# MCU_DBG.net
KiCad netlist of a schematic drawn in Altium Designer
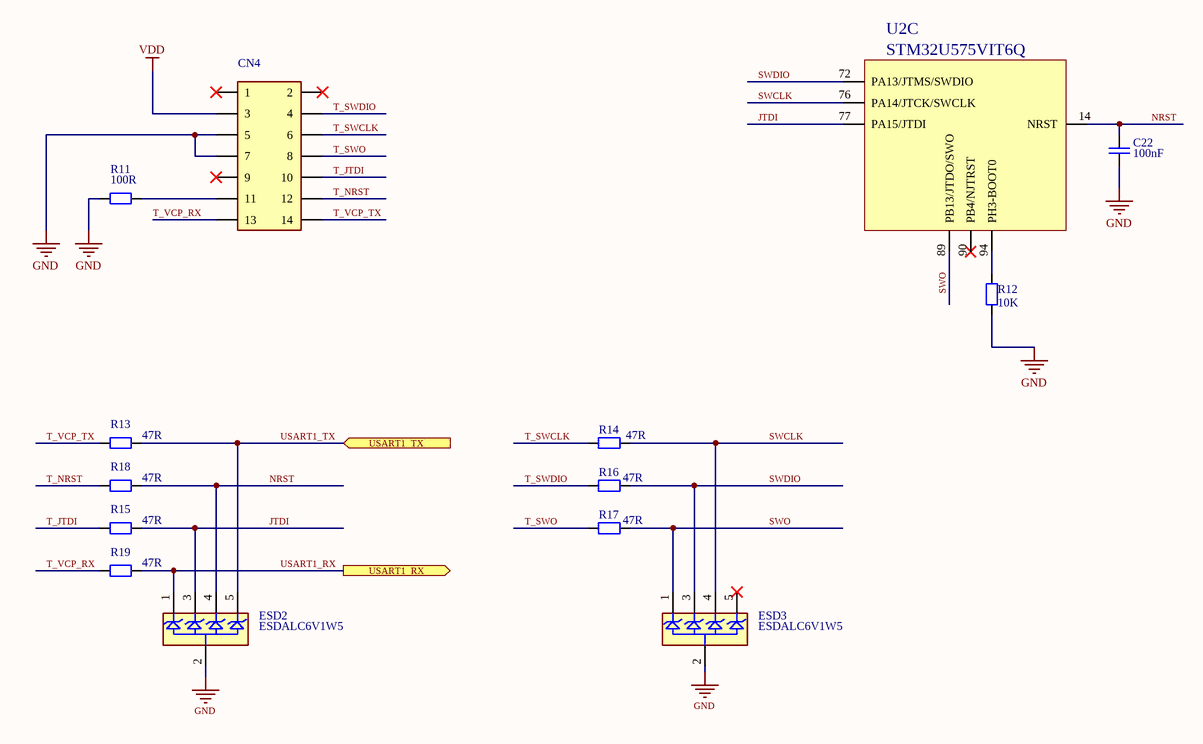
[diagram p0: MCU_DBG.SchDoc]

(export (version "E")
  (design (tool "Eeschema 10.0.6"))
  (components
    (comp (ref "C22")
      (value "100nF")
      (footprint "CAP_SM0805_YAGEOCC2_N")
      (description "CAP 100nF SM0805 X7R 50V YAGEO CC2")
      (fields
        (field (name "MANUFACTURER") "Yageo")
        (field (name "MANUFACTURER PART NUMBER") "CC0805KRX7R9BB104")
      )
      (libsource (lib "Yageo") (part "CC0805KRX7R9BB104"))
    )
    (comp (ref "CN4")
      (value "20021511-00014T4LF")
      (footprint "2002151100014T4LF")
      (description "1.27mm (0.05in.) pitch, Shrouded header, 14 contacts")
      (fields (field (name "MANUFACTURER") "Amphenol ICC"))
      (libsource (lib "header_shrouded") (part "20021511-00014T4LF"))
    )
    (comp (ref "ESD2")
      (value "ESDALC6V1W5")
      (footprint "ESDALC6V1W5")
      (fields (field (name "MANUFACTURER") "ST"))
      (libsource (lib "diode") (part "ESDALC6V1W5"))
    )
    (comp (ref "ESD3")
      (value "ESDALC6V1W5")
      (footprint "ESDALC6V1W5")
      (fields (field (name "MANUFACTURER") "ST"))
      (libsource (lib "diode") (part "ESDALC6V1W5"))
    )
    (comp (ref "R11")
      (value "100R")
      (footprint "RES_SM0805_YAGEORC_N")
      (description "RES 100R SM0805 YAGEO RC_L")
      (fields
        (field (name "MANUFACTURER") "Yageo")
        (field (name "MANUFACTURER PART NUMBER") "RC0805FR-07100RL")
      )
      (libsource (lib "Yageo") (part "RC0805FR-07100RL"))
    )
    (comp (ref "R12")
      (value "10K")
      (footprint "RES_SM0805_YAGEORC_N")
      (description "RES 10K SM0805 YAGEO RC_L")
      (fields
        (field (name "MANUFACTURER") "Yageo")
        (field (name "MANUFACTURER PART NUMBER") "RC0805FR-0710KL")
      )
      (libsource (lib "Yageo") (part "RC0805FR-0710KL"))
    )
    (comp (ref "R13")
      (value "47R")
      (footprint "RES_SM0805_YAGEORC_N")
      (description "RES 47R SM0805 YAGEO RC_L")
      (fields
        (field (name "MANUFACTURER") "Yageo")
        (field (name "MANUFACTURER PART NUMBER") "RC0805FR-0747RL")
      )
      (libsource (lib "Yageo") (part "RC0805FR-0747RL"))
    )
    (comp (ref "R14")
      (value "47R")
      (footprint "RES_SM0805_YAGEORC_N")
      (description "RES 47R SM0805 YAGEO RC_L")
      (fields
        (field (name "MANUFACTURER") "Yageo")
        (field (name "MANUFACTURER PART NUMBER") "RC0805FR-0747RL")
      )
      (libsource (lib "Yageo") (part "RC0805FR-0747RL"))
    )
    (comp (ref "R15")
      (value "47R")
      (footprint "RES_SM0805_YAGEORC_N")
      (description "RES 47R SM0805 YAGEO RC_L")
      (fields
        (field (name "MANUFACTURER") "Yageo")
        (field (name "MANUFACTURER PART NUMBER") "RC0805FR-0747RL")
      )
      (libsource (lib "Yageo") (part "RC0805FR-0747RL"))
    )
    (comp (ref "R16")
      (value "47R")
      (footprint "RES_SM0805_YAGEORC_N")
      (description "RES 47R SM0805 YAGEO RC_L")
      (fields
        (field (name "MANUFACTURER") "Yageo")
        (field (name "MANUFACTURER PART NUMBER") "RC0805FR-0747RL")
      )
      (libsource (lib "Yageo") (part "RC0805FR-0747RL"))
    )
    (comp (ref "R17")
      (value "47R")
      (footprint "RES_SM0805_YAGEORC_N")
      (description "RES 47R SM0805 YAGEO RC_L")
      (fields
        (field (name "MANUFACTURER") "Yageo")
        (field (name "MANUFACTURER PART NUMBER") "RC0805FR-0747RL")
      )
      (libsource (lib "Yageo") (part "RC0805FR-0747RL"))
    )
    (comp (ref "R18")
      (value "47R")
      (footprint "RES_SM0805_YAGEORC_N")
      (description "RES 47R SM0805 YAGEO RC_L")
      (fields
        (field (name "MANUFACTURER") "Yageo")
        (field (name "MANUFACTURER PART NUMBER") "RC0805FR-0747RL")
      )
      (libsource (lib "Yageo") (part "RC0805FR-0747RL"))
    )
    (comp (ref "R19")
      (value "47R")
      (footprint "RES_SM0805_YAGEORC_N")
      (description "RES 47R SM0805 YAGEO RC_L")
      (fields
        (field (name "MANUFACTURER") "Yageo")
        (field (name "MANUFACTURER PART NUMBER") "RC0805FR-0747RL")
      )
      (libsource (lib "Yageo") (part "RC0805FR-0747RL"))
    )
    (comp (ref "U2")
      (value "STM32U575VIT6Q")
      (footprint "STM32U575VI")
      (fields (field (name "MANUFACTURER") "ST"))
      (libsource (lib "Microcontroladores") (part "STM32U575VI_1"))
    )
  )
  (nets
    (net (code "1") (name "/JTDI") (class "Default")
      (node (ref "ESD2") (pin "3") (pinfunction "I/02_3") (pintype "passive"))
      (node (ref "R15") (pin "2") (pintype "passive"))
      (node (ref "U2") (pin "77") (pinfunction "PA15/JTDI_77") (pintype "passive"))
    )
    (net (code "2") (name "/NRST") (class "Default")
      (node (ref "C22") (pin "1") (pintype "passive"))
      (node (ref "ESD2") (pin "4") (pinfunction "I/03_4") (pintype "passive"))
      (node (ref "R18") (pin "2") (pintype "passive"))
      (node (ref "U2") (pin "14") (pinfunction "NRST_14") (pintype "passive"))
    )
    (net (code "3") (name "/SWCLK") (class "Default")
      (node (ref "ESD3") (pin "4") (pinfunction "I/03_4") (pintype "passive"))
      (node (ref "R14") (pin "2") (pintype "passive"))
      (node (ref "U2") (pin "76") (pinfunction "PA14/JTCK/SWCLK_76") (pintype "passive"))
    )
    (net (code "4") (name "/SWDIO") (class "Default")
      (node (ref "ESD3") (pin "3") (pinfunction "I/02_3") (pintype "passive"))
      (node (ref "R16") (pin "2") (pintype "passive"))
      (node (ref "U2") (pin "72") (pinfunction "PA13/JTMS/SWDIO_72") (pintype "passive"))
    )
    (net (code "5") (name "/SWO") (class "Default")
      (node (ref "ESD3") (pin "1") (pinfunction "I/01_1") (pintype "passive"))
      (node (ref "R17") (pin "2") (pintype "passive"))
      (node (ref "U2") (pin "89") (pinfunction "PB13/JTDO/SWO_89") (pintype "passive"))
    )
    (net (code "6") (name "/T_JTDI") (class "Default")
      (node (ref "CN4") (pin "10") (pinfunction "10_10") (pintype "passive"))
      (node (ref "R15") (pin "1") (pintype "passive"))
    )
    (net (code "7") (name "/T_NRST") (class "Default")
      (node (ref "CN4") (pin "12") (pinfunction "12_12") (pintype "passive"))
      (node (ref "R18") (pin "1") (pintype "passive"))
    )
    (net (code "8") (name "/T_SWCLK") (class "Default")
      (node (ref "CN4") (pin "6") (pinfunction "6_6") (pintype "passive"))
      (node (ref "R14") (pin "1") (pintype "passive"))
    )
    (net (code "9") (name "/T_SWDIO") (class "Default")
      (node (ref "CN4") (pin "4") (pinfunction "4_4") (pintype "passive"))
      (node (ref "R16") (pin "1") (pintype "passive"))
    )
    (net (code "10") (name "/T_SWO") (class "Default")
      (node (ref "CN4") (pin "8") (pinfunction "8_8") (pintype "passive"))
      (node (ref "R17") (pin "1") (pintype "passive"))
    )
    (net (code "11") (name "/T_VCP_RX") (class "Default")
      (node (ref "CN4") (pin "13") (pinfunction "13_13") (pintype "passive"))
      (node (ref "R19") (pin "1") (pintype "passive"))
    )
    (net (code "12") (name "/T_VCP_TX") (class "Default")
      (node (ref "CN4") (pin "14") (pinfunction "14_14") (pintype "passive"))
      (node (ref "R13") (pin "1") (pintype "passive"))
    )
    (net (code "13") (name "/USART1_RX") (class "Default")
      (node (ref "ESD2") (pin "1") (pinfunction "I/01_1") (pintype "passive"))
      (node (ref "R19") (pin "2") (pintype "passive"))
    )
    (net (code "14") (name "/USART1_TX") (class "Default")
      (node (ref "ESD2") (pin "5") (pinfunction "I/04_5") (pintype "passive"))
      (node (ref "R13") (pin "2") (pintype "passive"))
    )
    (net (code "15") (name "GND") (class "Default")
      (node (ref "C22") (pin "2") (pintype "passive"))
      (node (ref "CN4") (pin "5") (pinfunction "5_5") (pintype "passive"))
      (node (ref "CN4") (pin "7") (pinfunction "7_7") (pintype "passive"))
      (node (ref "ESD2") (pin "2") (pinfunction "GND_2") (pintype "passive"))
      (node (ref "ESD3") (pin "2") (pinfunction "GND_2") (pintype "passive"))
      (node (ref "R11") (pin "1") (pintype "passive"))
      (node (ref "R12") (pin "1") (pintype "passive"))
    )
    (net (code "16") (name "Net-(CN4-Pad11)") (class "Default")
      (node (ref "CN4") (pin "11") (pinfunction "11_11") (pintype "passive"))
      (node (ref "R11") (pin "2") (pintype "passive"))
    )
    (net (code "17") (name "Net-(U2C-PH3-BOOT0)") (class "Default")
      (node (ref "R12") (pin "2") (pintype "passive"))
      (node (ref "U2") (pin "94") (pinfunction "PH3-BOOT0_94") (pintype "passive"))
    )
    (net (code "18") (name "VDD") (class "Default")
      (node (ref "CN4") (pin "3") (pinfunction "3_3") (pintype "passive"))
    )
    (net (code "19") (name "unconnected-(CN4-Pad1)") (class "Default")
      (node (ref "CN4") (pin "1") (pinfunction "1_1") (pintype "passive+no_connect"))
    )
    (net (code "20") (name "unconnected-(CN4-Pad2)") (class "Default")
      (node (ref "CN4") (pin "2") (pinfunction "2_2") (pintype "passive+no_connect"))
    )
    (net (code "21") (name "unconnected-(CN4-Pad9)") (class "Default")
      (node (ref "CN4") (pin "9") (pinfunction "9_9") (pintype "passive+no_connect"))
    )
    (net (code "22") (name "unconnected-(ESD3-I{slash}04-Pad5)") (class "Default")
      (node (ref "ESD3") (pin "5") (pinfunction "I/04_5") (pintype "passive+no_connect"))
    )
    (net (code "23") (name "unconnected-(U2C-PB4{slash}NJTRST-Pad90)") (class "Default")
      (node (ref "U2") (pin "90") (pinfunction "PB4/NJTRST_90") (pintype "passive+no_connect"))
    )
  )
)
